# Bluetooth.net
KiCad netlist of a schematic drawn in Altium Designer
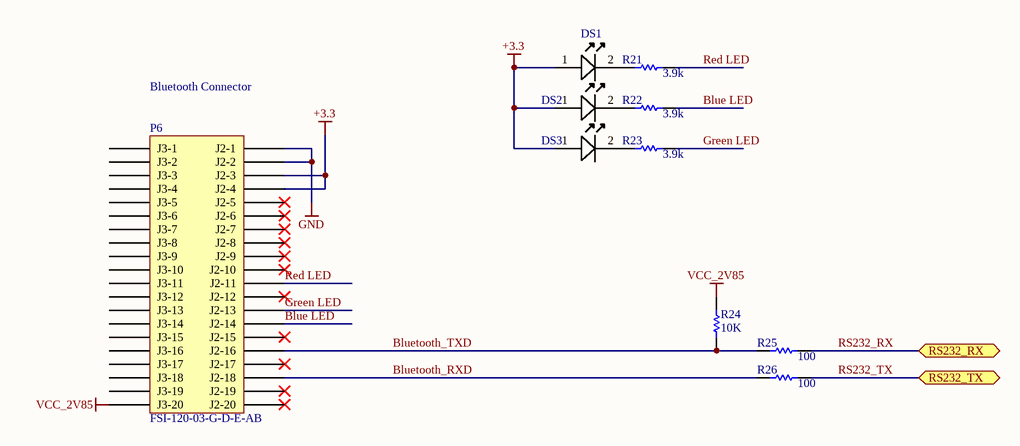
[diagram p0: Bluetooth.SchDoc]

(export (version "E")
  (design (tool "Eeschema 10.0.6"))
  (components
    (comp (ref "DS1")
      (value "Lite-On LTST-S220KGKT Green LED, 571 nm 2012 (0805) Side View, Rectangle Lens SMD package")
      (footprint "0805C_L")
      (fields
        (field (name "MANUFACTURER") "Vishay / Lite-On")
        (field (name "MANUFACTURER PART NUMBER") "LTST-S220KGKT")
      )
      (libsource (lib "*") (part "LED A/K"))
    )
    (comp (ref "DS2")
      (value "Lite-On LTST-S220KGKT Green LED, 571 nm 2012 (0805) Side View, Rectangle Lens SMD package")
      (footprint "0805C_L")
      (fields
        (field (name "MANUFACTURER") "Vishay / Lite-On")
        (field (name "MANUFACTURER PART NUMBER") "LTST-S220KGKT")
      )
      (libsource (lib "*") (part "LED A/K"))
    )
    (comp (ref "DS3")
      (value "Lite-On LTST-S220KGKT Green LED, 571 nm 2012 (0805) Side View, Rectangle Lens SMD package")
      (footprint "0805C_L")
      (fields
        (field (name "MANUFACTURER") "Vishay / Lite-On")
        (field (name "MANUFACTURER PART NUMBER") "LTST-S220KGKT")
      )
      (libsource (lib "*") (part "LED A/K"))
    )
    (comp (ref "P6")
      (value "FSI-120-03-G-D-E-AB")
      (footprint "FSI-120-03-G-D-E-AB")
      (fields (field (name "SUPPLIER PART NUMBER 1") "FSI-120-03-G-D-E-AB"))
      (libsource (lib "ZLS_Schematic_lib") (part "FSI-120-03-G-D-E-AB"))
    )
    (comp (ref "R21")
      (value "3.9k")
      (footprint "RESC0805(2012)_L")
      (description "2R55 0.125W 1% 0805 (2012 Metric)  SMD")
      (fields (field (name "TOLERANCE") "1 %") (field (name "POWER") "0.125 W"))
      (libsource (lib "Altium Content Vault") (part "CMP-1013-00215-1"))
    )
    (comp (ref "R22")
      (value "3.9k")
      (footprint "RESC0805(2012)_L")
      (description "2R55 0.125W 1% 0805 (2012 Metric)  SMD")
      (fields (field (name "TOLERANCE") "1 %") (field (name "POWER") "0.125 W"))
      (libsource (lib "Altium Content Vault") (part "CMP-1013-00215-1"))
    )
    (comp (ref "R23")
      (value "3.9k")
      (footprint "RESC0805(2012)_L")
      (description "2R55 0.125W 1% 0805 (2012 Metric)  SMD")
      (fields (field (name "TOLERANCE") "1 %") (field (name "POWER") "0.125 W"))
      (libsource (lib "Altium Content Vault") (part "CMP-1013-00215-1"))
    )
    (comp (ref "R24")
      (value "10K")
      (footprint "RESC0805(2012)_L")
      (description "2R55 0.125W 1% 0805 (2012 Metric)  SMD")
      (fields (field (name "TOLERANCE") "1 %") (field (name "POWER") "0.125 W"))
      (libsource (lib "Altium Content Vault") (part "CMP-1013-00215-1"))
    )
    (comp (ref "R25")
      (value "100")
      (footprint "RESC0805(2012)_L")
      (description "2R55 0.125W 1% 0805 (2012 Metric)  SMD")
      (fields (field (name "TOLERANCE") "1 %") (field (name "POWER") "0.125 W"))
      (libsource (lib "Altium Content Vault") (part "CMP-1013-00215-1"))
    )
    (comp (ref "R26")
      (value "100")
      (footprint "RESC0805(2012)_L")
      (description "2R55 0.125W 1% 0805 (2012 Metric)  SMD")
      (fields (field (name "TOLERANCE") "1 %") (field (name "POWER") "0.125 W"))
      (libsource (lib "Altium Content Vault") (part "CMP-1013-00215-1"))
    )
  )
  (nets
    (net (code "1") (name "+3.3") (class "Default")
      (node (ref "DS1") (pin "1") (pinfunction "A_1") (pintype "passive"))
      (node (ref "DS2") (pin "1") (pinfunction "A_1") (pintype "passive"))
      (node (ref "DS3") (pin "1") (pinfunction "A_1") (pintype "passive"))
      (node (ref "P6") (pin "J2-3") (pinfunction "J2-3_J2-3") (pintype "passive"))
      (node (ref "P6") (pin "J2-4") (pinfunction "J2-4_J2-4") (pintype "passive"))
    )
    (net (code "2") (name "/Blue LED") (class "Default")
      (node (ref "P6") (pin "J2-14") (pinfunction "J2-14_J2-14") (pintype "passive"))
      (node (ref "R22") (pin "1") (pinfunction "1_1") (pintype "passive"))
    )
    (net (code "3") (name "/Bluetooth_RXD") (class "Default")
      (node (ref "P6") (pin "J2-18") (pinfunction "J2-18_J2-18") (pintype "passive"))
      (node (ref "R26") (pin "2") (pinfunction "2_2") (pintype "passive"))
    )
    (net (code "4") (name "/Bluetooth_TXD") (class "Default")
      (node (ref "P6") (pin "J2-16") (pinfunction "J2-16_J2-16") (pintype "passive"))
      (node (ref "R24") (pin "2") (pinfunction "2_2") (pintype "passive"))
      (node (ref "R25") (pin "2") (pinfunction "2_2") (pintype "passive"))
    )
    (net (code "5") (name "/Green LED") (class "Default")
      (node (ref "P6") (pin "J2-13") (pinfunction "J2-13_J2-13") (pintype "passive"))
      (node (ref "R23") (pin "1") (pinfunction "1_1") (pintype "passive"))
    )
    (net (code "6") (name "/RS232_RX") (class "Default")
      (node (ref "R25") (pin "1") (pinfunction "1_1") (pintype "passive"))
    )
    (net (code "7") (name "/RS232_TX") (class "Default")
      (node (ref "R26") (pin "1") (pinfunction "1_1") (pintype "passive"))
    )
    (net (code "8") (name "/Red LED") (class "Default")
      (node (ref "P6") (pin "J2-11") (pinfunction "J2-11_J2-11") (pintype "passive"))
      (node (ref "R21") (pin "1") (pinfunction "1_1") (pintype "passive"))
    )
    (net (code "9") (name "GND") (class "Default")
      (node (ref "P6") (pin "J2-1") (pinfunction "J2-1_J2-1") (pintype "passive"))
      (node (ref "P6") (pin "J2-2") (pinfunction "J2-2_J2-2") (pintype "passive"))
    )
    (net (code "10") (name "Net-(DS1-K)") (class "Default")
      (node (ref "DS1") (pin "2") (pinfunction "K_2") (pintype "passive"))
      (node (ref "R21") (pin "2") (pinfunction "2_2") (pintype "passive"))
    )
    (net (code "11") (name "Net-(DS2-K)") (class "Default")
      (node (ref "DS2") (pin "2") (pinfunction "K_2") (pintype "passive"))
      (node (ref "R22") (pin "2") (pinfunction "2_2") (pintype "passive"))
    )
    (net (code "12") (name "Net-(DS3-K)") (class "Default")
      (node (ref "DS3") (pin "2") (pinfunction "K_2") (pintype "passive"))
      (node (ref "R23") (pin "2") (pinfunction "2_2") (pintype "passive"))
    )
    (net (code "13") (name "VCC_2V85") (class "Default")
      (node (ref "P6") (pin "J3-20") (pinfunction "J3-20_J3-20") (pintype "passive"))
      (node (ref "R24") (pin "1") (pinfunction "1_1") (pintype "passive"))
    )
    (net (code "14") (name "unconnected-(P6-PadJ2-5)") (class "Default")
      (node (ref "P6") (pin "J2-5") (pinfunction "J2-5_J2-5") (pintype "passive+no_connect"))
    )
    (net (code "15") (name "unconnected-(P6-PadJ2-6)") (class "Default")
      (node (ref "P6") (pin "J2-6") (pinfunction "J2-6_J2-6") (pintype "passive+no_connect"))
    )
    (net (code "16") (name "unconnected-(P6-PadJ2-7)") (class "Default")
      (node (ref "P6") (pin "J2-7") (pinfunction "J2-7_J2-7") (pintype "passive+no_connect"))
    )
    (net (code "17") (name "unconnected-(P6-PadJ2-8)") (class "Default")
      (node (ref "P6") (pin "J2-8") (pinfunction "J2-8_J2-8") (pintype "passive+no_connect"))
    )
    (net (code "18") (name "unconnected-(P6-PadJ2-9)") (class "Default")
      (node (ref "P6") (pin "J2-9") (pinfunction "J2-9_J2-9") (pintype "passive+no_connect"))
    )
    (net (code "19") (name "unconnected-(P6-PadJ2-10)") (class "Default")
      (node (ref "P6") (pin "J2-10") (pinfunction "J2-10_J2-10") (pintype "passive+no_connect"))
    )
    (net (code "20") (name "unconnected-(P6-PadJ2-12)") (class "Default")
      (node (ref "P6") (pin "J2-12") (pinfunction "J2-12_J2-12") (pintype "passive+no_connect"))
    )
    (net (code "21") (name "unconnected-(P6-PadJ2-15)") (class "Default")
      (node (ref "P6") (pin "J2-15") (pinfunction "J2-15_J2-15") (pintype "passive+no_connect"))
    )
    (net (code "22") (name "unconnected-(P6-PadJ2-17)") (class "Default")
      (node (ref "P6") (pin "J2-17") (pinfunction "J2-17_J2-17") (pintype "passive+no_connect"))
    )
    (net (code "23") (name "unconnected-(P6-PadJ2-19)") (class "Default")
      (node (ref "P6") (pin "J2-19") (pinfunction "J2-19_J2-19") (pintype "passive+no_connect"))
    )
    (net (code "24") (name "unconnected-(P6-PadJ2-20)") (class "Default")
      (node (ref "P6") (pin "J2-20") (pinfunction "J2-20_J2-20") (pintype "passive+no_connect"))
    )
    (net (code "25") (name "unconnected-(P6-PadJ3-1)") (class "Default")
      (node (ref "P6") (pin "J3-1") (pinfunction "J3-1_J3-1") (pintype "passive"))
    )
    (net (code "26") (name "unconnected-(P6-PadJ3-2)") (class "Default")
      (node (ref "P6") (pin "J3-2") (pinfunction "J3-2_J3-2") (pintype "passive"))
    )
    (net (code "27") (name "unconnected-(P6-PadJ3-3)") (class "Default")
      (node (ref "P6") (pin "J3-3") (pinfunction "J3-3_J3-3") (pintype "passive"))
    )
    (net (code "28") (name "unconnected-(P6-PadJ3-4)") (class "Default")
      (node (ref "P6") (pin "J3-4") (pinfunction "J3-4_J3-4") (pintype "passive"))
    )
    (net (code "29") (name "unconnected-(P6-PadJ3-5)") (class "Default")
      (node (ref "P6") (pin "J3-5") (pinfunction "J3-5_J3-5") (pintype "passive"))
    )
    (net (code "30") (name "unconnected-(P6-PadJ3-6)") (class "Default")
      (node (ref "P6") (pin "J3-6") (pinfunction "J3-6_J3-6") (pintype "passive"))
    )
    (net (code "31") (name "unconnected-(P6-PadJ3-7)") (class "Default")
      (node (ref "P6") (pin "J3-7") (pinfunction "J3-7_J3-7") (pintype "passive"))
    )
    (net (code "32") (name "unconnected-(P6-PadJ3-8)") (class "Default")
      (node (ref "P6") (pin "J3-8") (pinfunction "J3-8_J3-8") (pintype "passive"))
    )
    (net (code "33") (name "unconnected-(P6-PadJ3-9)") (class "Default")
      (node (ref "P6") (pin "J3-9") (pinfunction "J3-9_J3-9") (pintype "passive"))
    )
    (net (code "34") (name "unconnected-(P6-PadJ3-10)") (class "Default")
      (node (ref "P6") (pin "J3-10") (pinfunction "J3-10_J3-10") (pintype "passive"))
    )
    (net (code "35") (name "unconnected-(P6-PadJ3-11)") (class "Default")
      (node (ref "P6") (pin "J3-11") (pinfunction "J3-11_J3-11") (pintype "passive"))
    )
    (net (code "36") (name "unconnected-(P6-PadJ3-12)") (class "Default")
      (node (ref "P6") (pin "J3-12") (pinfunction "J3-12_J3-12") (pintype "passive"))
    )
    (net (code "37") (name "unconnected-(P6-PadJ3-13)") (class "Default")
      (node (ref "P6") (pin "J3-13") (pinfunction "J3-13_J3-13") (pintype "passive"))
    )
    (net (code "38") (name "unconnected-(P6-PadJ3-14)") (class "Default")
      (node (ref "P6") (pin "J3-14") (pinfunction "J3-14_J3-14") (pintype "passive"))
    )
    (net (code "39") (name "unconnected-(P6-PadJ3-15)") (class "Default")
      (node (ref "P6") (pin "J3-15") (pinfunction "J3-15_J3-15") (pintype "passive"))
    )
    (net (code "40") (name "unconnected-(P6-PadJ3-16)") (class "Default")
      (node (ref "P6") (pin "J3-16") (pinfunction "J3-16_J3-16") (pintype "passive"))
    )
    (net (code "41") (name "unconnected-(P6-PadJ3-17)") (class "Default")
      (node (ref "P6") (pin "J3-17") (pinfunction "J3-17_J3-17") (pintype "passive"))
    )
    (net (code "42") (name "unconnected-(P6-PadJ3-18)") (class "Default")
      (node (ref "P6") (pin "J3-18") (pinfunction "J3-18_J3-18") (pintype "passive"))
    )
    (net (code "43") (name "unconnected-(P6-PadJ3-19)") (class "Default")
      (node (ref "P6") (pin "J3-19") (pinfunction "J3-19_J3-19") (pintype "passive"))
    )
  )
)
